# cbm_usb_v1_0a.net
KiCad netlist of a schematic drawn in EAGLE
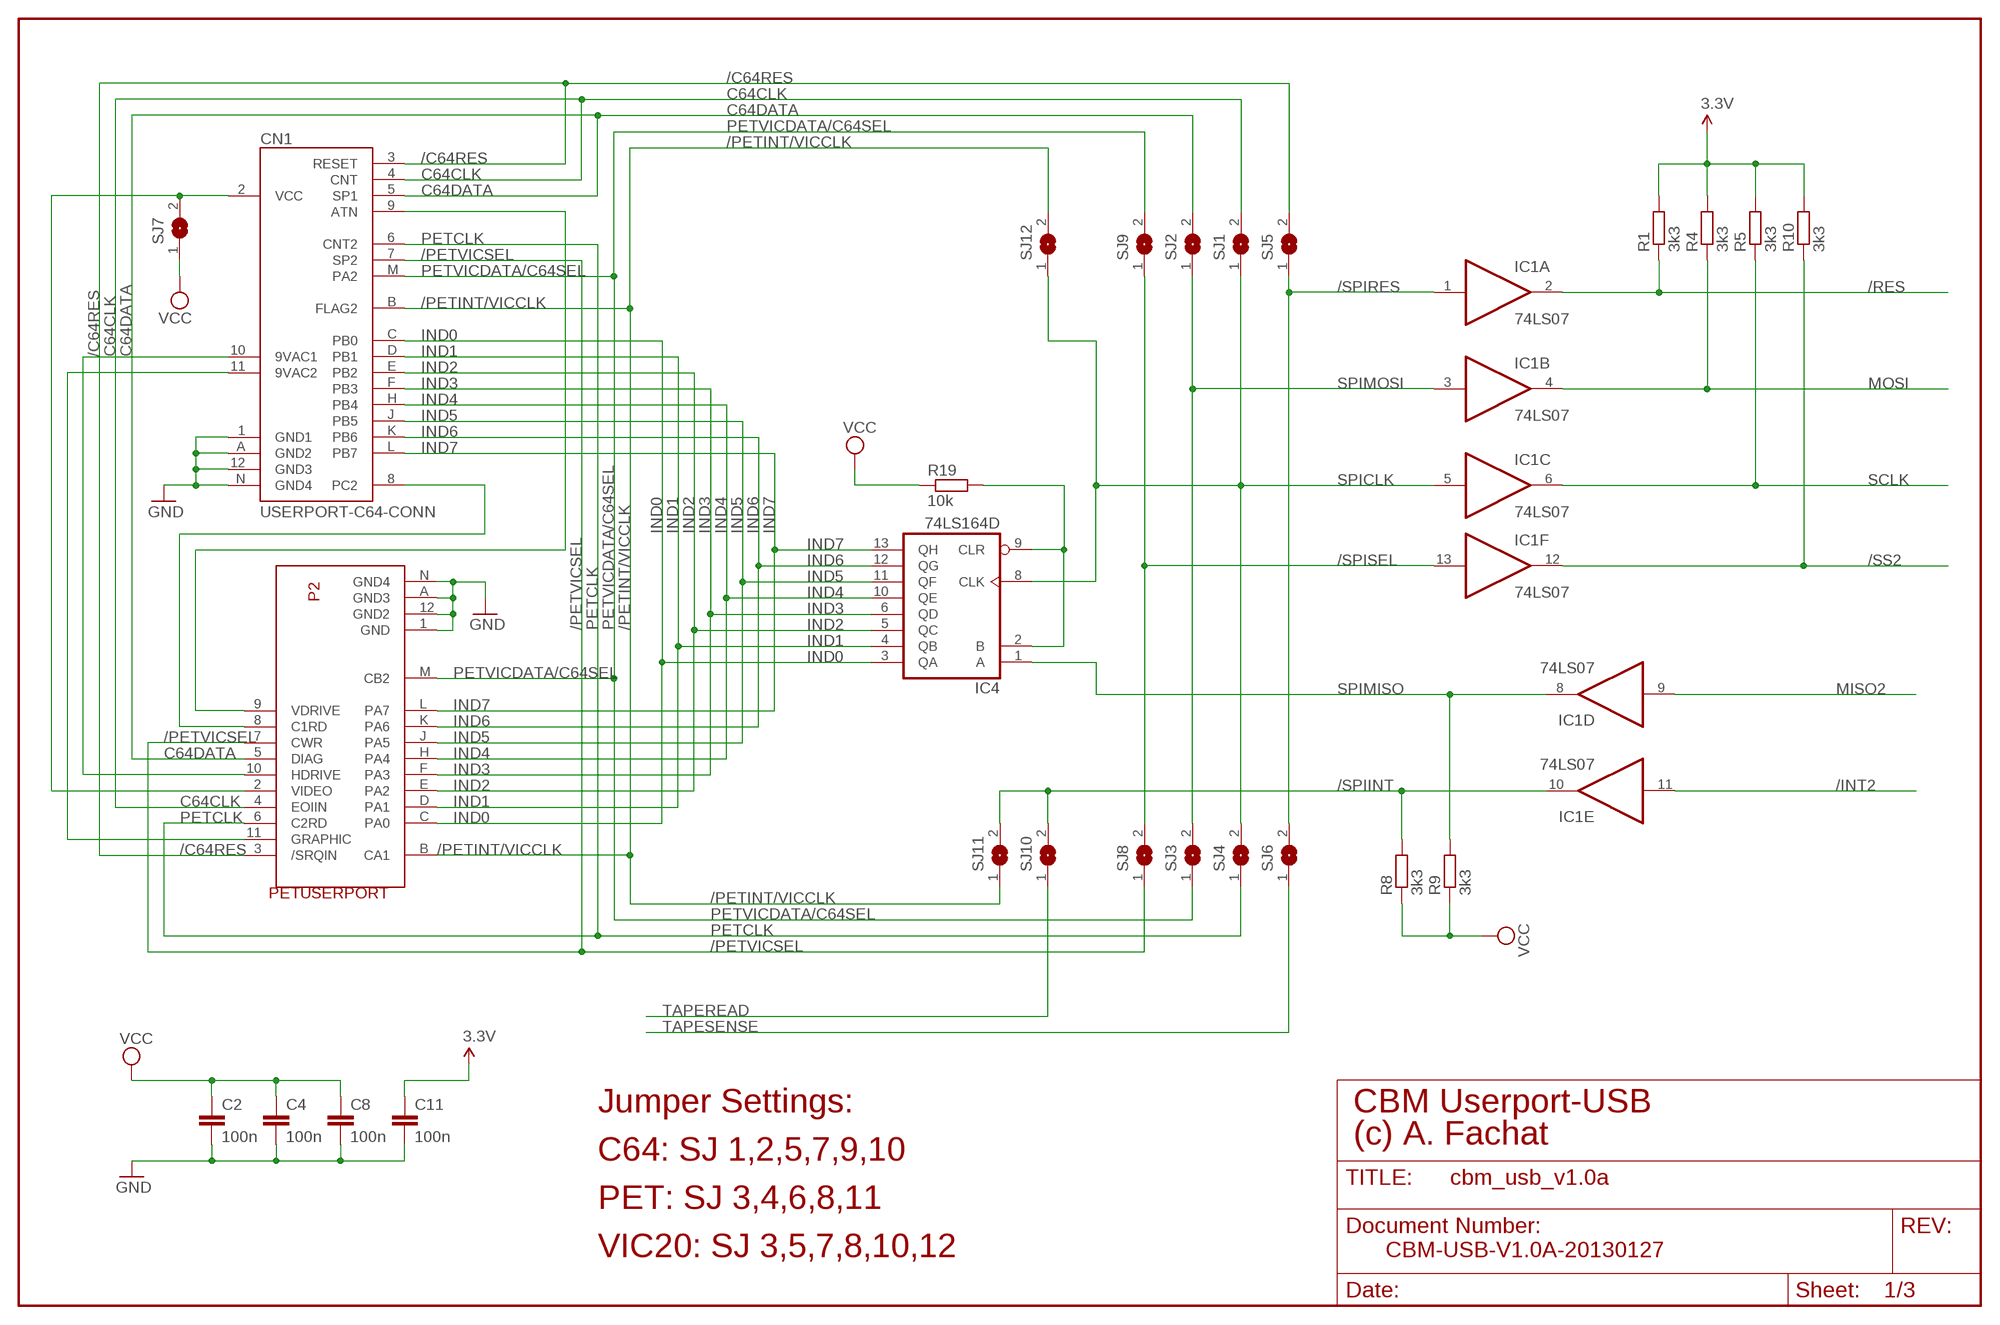
[diagram p0: schematic, sheet 1]
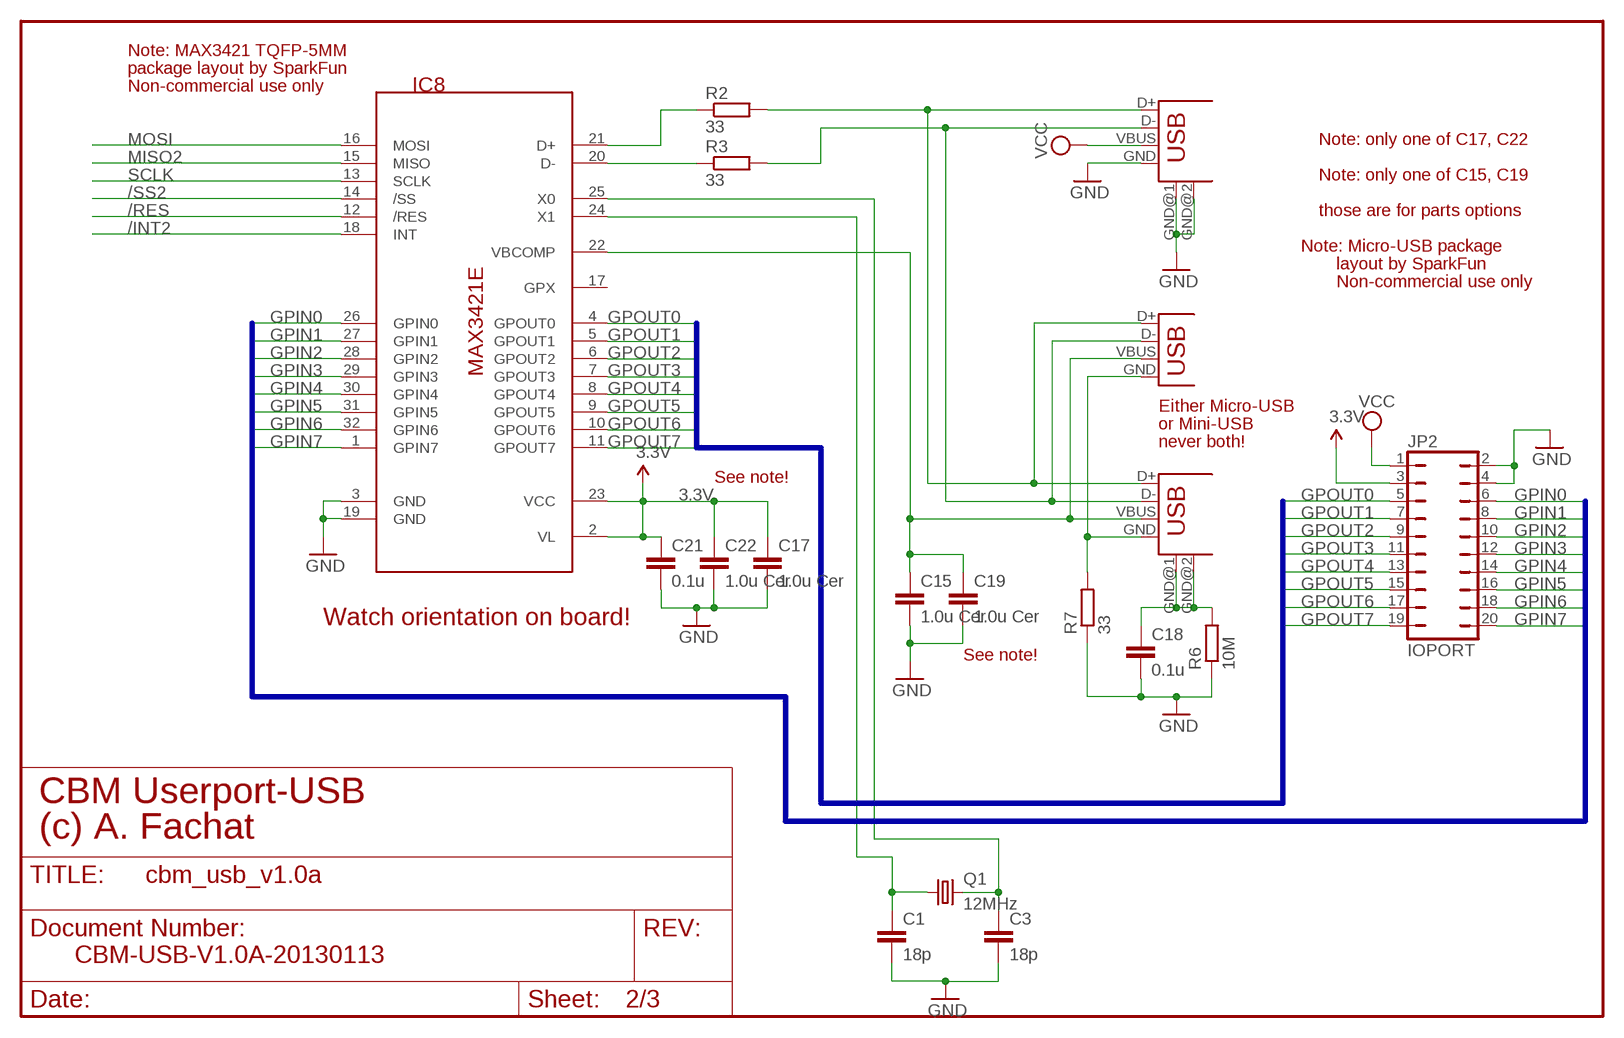
[diagram p1: schematic, sheet 2]
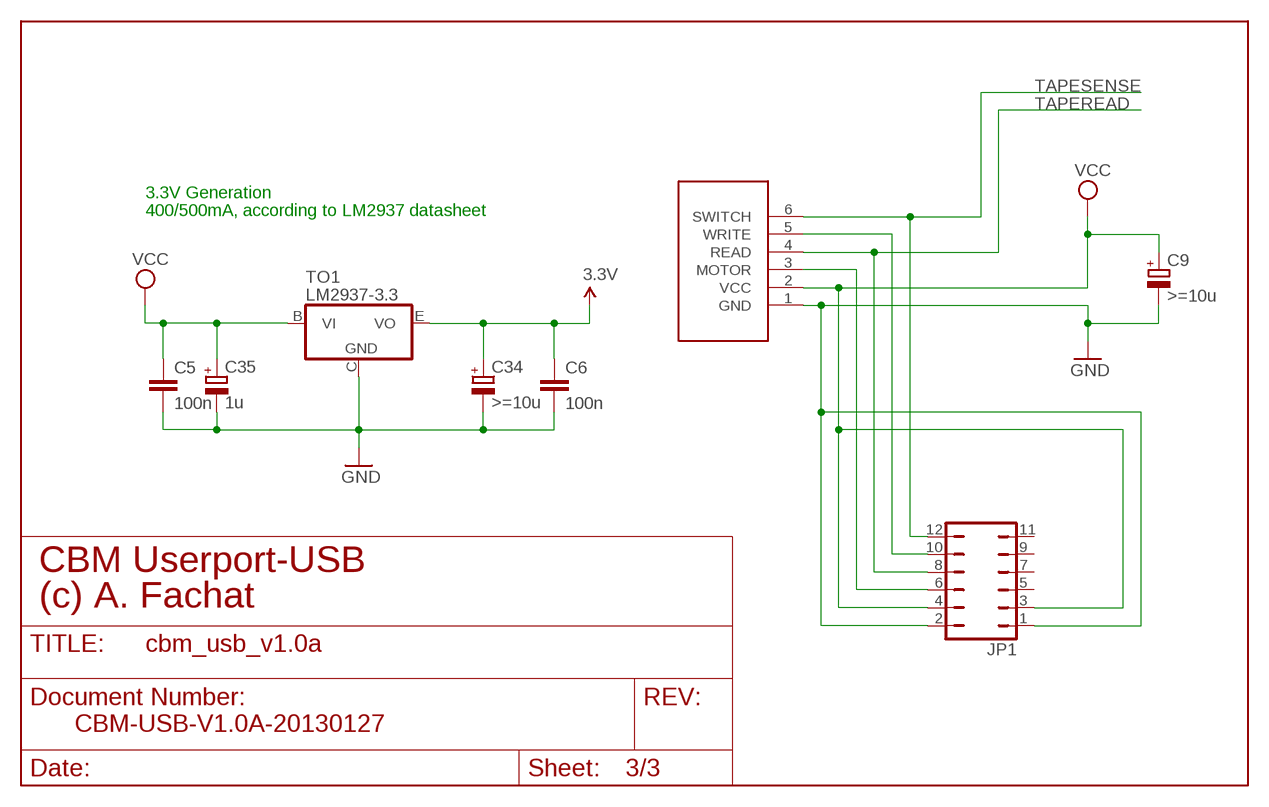
[diagram p2: schematic, sheet 3]

(export (version "E")
  (design (tool "Eeschema 10.0.6"))
  (components
    (comp (ref "C5")
      (value "100n")
      (footprint "eagle-import:C050-025X075")
      (libsource (lib "eagle-import") (part "C-EU050-025X075"))
    )
    (comp (ref "C6")
      (value "100n")
      (footprint "eagle-import:C050-025X075")
      (libsource (lib "eagle-import") (part "C-EU050-025X075"))
    )
    (comp (ref "C9")
      (value ">=10u")
      (footprint "eagle-import:E5-10,5")
      (libsource (lib "eagle-import") (part "CPOL-EUE5-10.5"))
    )
    (comp (ref "C34")
      (value ">=10u")
      (footprint "eagle-import:E5-8,5")
      (libsource (lib "eagle-import") (part "CPOL-EUE5-8.5"))
    )
    (comp (ref "C35")
      (value "1u")
      (footprint "eagle-import:E5-8,5")
      (libsource (lib "eagle-import") (part "CPOL-EUE5-8.5"))
    )
    (comp (ref "JP1")
      (value "JP6Q")
      (footprint "eagle-import:JP6Q")
      (libsource (lib "eagle-import") (part "JP6Q"))
    )
    (comp (ref "P3")
      (value "CBMTAPE")
      (footprint "eagle-import:JP6")
      (libsource (lib "eagle-import") (part "CBMTAPE"))
    )
    (comp (ref "TO1")
      (value "LM2937-3.3")
      (footprint "eagle-import:TO220H")
      (libsource (lib "eagle-import") (part "LM2937"))
    )
    (comp (ref "C2")
      (value "100n")
      (footprint "eagle-import:C050-025X075")
      (libsource (lib "eagle-import") (part "C-EU050-025X075"))
    )
    (comp (ref "C4")
      (value "100n")
      (footprint "eagle-import:C050-025X075")
      (libsource (lib "eagle-import") (part "C-EU050-025X075"))
    )
    (comp (ref "C8")
      (value "100n")
      (footprint "eagle-import:C050-025X075")
      (libsource (lib "eagle-import") (part "C-EU050-025X075"))
    )
    (comp (ref "C11")
      (value "100n")
      (footprint "eagle-import:C050-025X075")
      (libsource (lib "eagle-import") (part "C-EU050-025X075"))
    )
    (comp (ref "CN1")
      (value "USERPORT-C64-CONN")
      (footprint "eagle-import:UPS24CONN")
      (libsource (lib "eagle-import") (part "USERPORT-C64-CONN"))
    )
    (comp (ref "IC1")
      (value "74LS07")
      (footprint "eagle-import:SO14")
      (libsource (lib "eagle-import") (part "7407DLS"))
    )
    (comp (ref "IC4")
      (value "74LS164D")
      (footprint "eagle-import:SO14")
      (libsource (lib "eagle-import") (part "74164DLS"))
    )
    (comp (ref "P2")
      (value "PETUSERPORT")
      (footprint "eagle-import:FLAT24")
      (libsource (lib "eagle-import") (part "PETUSERPORT"))
    )
    (comp (ref "R1")
      (value "3k3")
      (footprint "eagle-import:0204_7")
      (libsource (lib "eagle-import") (part "R-EU_0204/7"))
    )
    (comp (ref "R4")
      (value "3k3")
      (footprint "eagle-import:0204_7")
      (libsource (lib "eagle-import") (part "R-EU_0204/7"))
    )
    (comp (ref "R5")
      (value "3k3")
      (footprint "eagle-import:0204_7")
      (libsource (lib "eagle-import") (part "R-EU_0204/7"))
    )
    (comp (ref "R8")
      (value "3k3")
      (footprint "eagle-import:0204_7")
      (libsource (lib "eagle-import") (part "R-EU_0204/7"))
    )
    (comp (ref "R9")
      (value "3k3")
      (footprint "eagle-import:0204_7")
      (libsource (lib "eagle-import") (part "R-EU_0204/7"))
    )
    (comp (ref "R10")
      (value "3k3")
      (footprint "eagle-import:0204_7")
      (libsource (lib "eagle-import") (part "R-EU_0204/7"))
    )
    (comp (ref "R19")
      (value "10k")
      (footprint "eagle-import:0204_7")
      (libsource (lib "eagle-import") (part "R-EU_0204/7"))
    )
    (comp (ref "SJ1")
      (value "SJW")
      (footprint "eagle-import:SJW")
      (libsource (lib "eagle-import") (part "SJW"))
    )
    (comp (ref "SJ2")
      (value "SJW")
      (footprint "eagle-import:SJW")
      (libsource (lib "eagle-import") (part "SJW"))
    )
    (comp (ref "SJ3")
      (value "SJW")
      (footprint "eagle-import:SJW")
      (libsource (lib "eagle-import") (part "SJW"))
    )
    (comp (ref "SJ4")
      (value "SJW")
      (footprint "eagle-import:SJW")
      (libsource (lib "eagle-import") (part "SJW"))
    )
    (comp (ref "SJ5")
      (value "SJW")
      (footprint "eagle-import:SJW")
      (libsource (lib "eagle-import") (part "SJW"))
    )
    (comp (ref "SJ6")
      (value "SJW")
      (footprint "eagle-import:SJW")
      (libsource (lib "eagle-import") (part "SJW"))
    )
    (comp (ref "SJ7")
      (value "SJW")
      (footprint "eagle-import:SJW")
      (libsource (lib "eagle-import") (part "SJW"))
    )
    (comp (ref "SJ8")
      (value "SJW")
      (footprint "eagle-import:SJW")
      (libsource (lib "eagle-import") (part "SJW"))
    )
    (comp (ref "SJ9")
      (value "SJW")
      (footprint "eagle-import:SJW")
      (libsource (lib "eagle-import") (part "SJW"))
    )
    (comp (ref "SJ10")
      (value "SJW")
      (footprint "eagle-import:SJW")
      (libsource (lib "eagle-import") (part "SJW"))
    )
    (comp (ref "SJ11")
      (value "SJW")
      (footprint "eagle-import:SJW")
      (libsource (lib "eagle-import") (part "SJW"))
    )
    (comp (ref "SJ12")
      (value "SJW")
      (footprint "eagle-import:SJW")
      (libsource (lib "eagle-import") (part "SJW"))
    )
    (comp (ref "C1")
      (value "18p")
      (footprint "eagle-import:C050-025X075")
      (libsource (lib "eagle-import") (part "C-EU050-025X075"))
    )
    (comp (ref "C3")
      (value "18p")
      (footprint "eagle-import:C050-025X075")
      (libsource (lib "eagle-import") (part "C-EU050-025X075"))
    )
    (comp (ref "C15")
      (value "1.0u Cer")
      (footprint "eagle-import:C0603")
      (libsource (lib "eagle-import") (part "C-EUC0603"))
    )
    (comp (ref "C17")
      (value "1.0u Cer")
      (footprint "eagle-import:C050-024X044")
      (libsource (lib "eagle-import") (part "C-EU050-024X044"))
    )
    (comp (ref "C18")
      (value "0.1u")
      (footprint "eagle-import:C050-025X075")
      (libsource (lib "eagle-import") (part "C-EU050-025X075"))
    )
    (comp (ref "C19")
      (value "1.0u Cer")
      (footprint "eagle-import:C050-024X044")
      (libsource (lib "eagle-import") (part "C-EU050-024X044"))
    )
    (comp (ref "C21")
      (value "0.1u")
      (footprint "eagle-import:C050-025X075")
      (libsource (lib "eagle-import") (part "C-EU050-025X075"))
    )
    (comp (ref "C22")
      (value "1.0u Cer")
      (footprint "eagle-import:C0603")
      (libsource (lib "eagle-import") (part "C-EUC0603"))
    )
    (comp (ref "IC8")
      (value "MAX3421E")
      (footprint "eagle-import:TQFP32-5MM")
      (libsource (lib "eagle-import") (part "MAX3421E"))
    )
    (comp (ref "JP2")
      (value "IOPORT")
      (footprint "eagle-import:JP10Q")
      (libsource (lib "eagle-import") (part "JP10Q"))
    )
    (comp (ref "Q1")
      (value "12MHz")
      (footprint "eagle-import:HC49U70")
      (libsource (lib "eagle-import") (part "CRYSTALHC49U70"))
    )
    (comp (ref "R2")
      (value "33")
      (footprint "eagle-import:0204_7")
      (libsource (lib "eagle-import") (part "R-EU_0204/7"))
    )
    (comp (ref "R3")
      (value "33")
      (footprint "eagle-import:0204_7")
      (libsource (lib "eagle-import") (part "R-EU_0204/7"))
    )
    (comp (ref "R6")
      (value "10M")
      (footprint "eagle-import:0204_7")
      (libsource (lib "eagle-import") (part "R-EU_0204/7"))
    )
    (comp (ref "R7")
      (value "33")
      (footprint "eagle-import:0204_7")
      (libsource (lib "eagle-import") (part "R-EU_0204/7"))
    )
    (comp (ref "USB1")
      (value "USB-A-H")
      (footprint "eagle-import:USB-A-H")
      (libsource (lib "eagle-import") (part "con-usb-2_USB-A-H"))
    )
    (comp (ref "USB2")
      (value "USB-MB-H")
      (footprint "eagle-import:USB-MB-H")
      (libsource (lib "eagle-import") (part "con-usb-2_USB-MB-H"))
    )
    (comp (ref "X1")
      (value "USB-MICROB")
      (footprint "eagle-import:USB-MICROB")
      (libsource (lib "eagle-import") (part "USB-MICROB"))
    )
  )
  (nets
    (net (code "1") (name "3.3V") (class "Default")
      (node (ref "C11") (pin "1") (pinfunction "1_1") (pintype "passive"))
      (node (ref "C17") (pin "1") (pinfunction "1_1") (pintype "passive"))
      (node (ref "C21") (pin "1") (pinfunction "1_1") (pintype "passive"))
      (node (ref "C22") (pin "1") (pinfunction "1_1") (pintype "passive"))
      (node (ref "C34") (pin "+") (pinfunction "+_+") (pintype "passive"))
      (node (ref "C6") (pin "1") (pinfunction "1_1") (pintype "passive"))
      (node (ref "IC8") (pin "2") (pinfunction "VL_2") (pintype "power_in"))
      (node (ref "IC8") (pin "23") (pinfunction "VCC_23") (pintype "power_in"))
      (node (ref "JP2") (pin "3") (pinfunction "3_3") (pintype "passive"))
      (node (ref "R1") (pin "2") (pinfunction "2_2") (pintype "passive"))
      (node (ref "R10") (pin "2") (pinfunction "2_2") (pintype "passive"))
      (node (ref "R4") (pin "2") (pinfunction "2_2") (pintype "passive"))
      (node (ref "R5") (pin "2") (pinfunction "2_2") (pintype "passive"))
      (node (ref "TO1") (pin "E") (pinfunction "VO_E") (pintype "passive"))
    )
    (net (code "2") (name "C64CLK") (class "Default")
      (node (ref "CN1") (pin "4") (pinfunction "CNT_4") (pintype "bidirectional"))
      (node (ref "P2") (pin "4") (pinfunction "EOIIN_4") (pintype "bidirectional"))
      (node (ref "SJ1") (pin "2") (pinfunction "2_2") (pintype "passive"))
    )
    (net (code "3") (name "C64DATA") (class "Default")
      (node (ref "CN1") (pin "5") (pinfunction "SP1_5") (pintype "bidirectional"))
      (node (ref "P2") (pin "5") (pinfunction "DIAG_5") (pintype "bidirectional"))
      (node (ref "SJ2") (pin "2") (pinfunction "2_2") (pintype "passive"))
    )
    (net (code "4") (name "GND") (class "Default")
      (node (ref "C1") (pin "2") (pinfunction "2_2") (pintype "passive"))
      (node (ref "C11") (pin "2") (pinfunction "2_2") (pintype "passive"))
      (node (ref "C15") (pin "2") (pinfunction "2_2") (pintype "passive"))
      (node (ref "C17") (pin "2") (pinfunction "2_2") (pintype "passive"))
      (node (ref "C18") (pin "2") (pinfunction "2_2") (pintype "passive"))
      (node (ref "C19") (pin "2") (pinfunction "2_2") (pintype "passive"))
      (node (ref "C2") (pin "2") (pinfunction "2_2") (pintype "passive"))
      (node (ref "C21") (pin "2") (pinfunction "2_2") (pintype "passive"))
      (node (ref "C22") (pin "2") (pinfunction "2_2") (pintype "passive"))
      (node (ref "C3") (pin "2") (pinfunction "2_2") (pintype "passive"))
      (node (ref "C34") (pin "-") (pinfunction "-_-") (pintype "passive"))
      (node (ref "C35") (pin "-") (pinfunction "-_-") (pintype "passive"))
      (node (ref "C4") (pin "2") (pinfunction "2_2") (pintype "passive"))
      (node (ref "C5") (pin "2") (pinfunction "2_2") (pintype "passive"))
      (node (ref "C6") (pin "2") (pinfunction "2_2") (pintype "passive"))
      (node (ref "C8") (pin "2") (pinfunction "2_2") (pintype "passive"))
      (node (ref "C9") (pin "-") (pinfunction "-_-") (pintype "passive"))
      (node (ref "CN1") (pin "1") (pinfunction "GND1_1") (pintype "passive"))
      (node (ref "CN1") (pin "12") (pinfunction "GND3_12") (pintype "passive"))
      (node (ref "CN1") (pin "A") (pinfunction "GND2_A") (pintype "passive"))
      (node (ref "CN1") (pin "N") (pinfunction "GND4_N") (pintype "passive"))
      (node (ref "IC8") (pin "19") (pinfunction "GND_19") (pintype "power_in"))
      (node (ref "IC8") (pin "3") (pinfunction "GND_3") (pintype "power_in"))
      (node (ref "JP1") (pin "1") (pinfunction "1_1") (pintype "passive"))
      (node (ref "JP1") (pin "2") (pinfunction "2_2") (pintype "passive"))
      (node (ref "JP2") (pin "2") (pinfunction "2_2") (pintype "passive"))
      (node (ref "JP2") (pin "4") (pinfunction "4_4") (pintype "passive"))
      (node (ref "P2") (pin "1") (pinfunction "GND_1") (pintype "bidirectional"))
      (node (ref "P2") (pin "12") (pinfunction "GND2_12") (pintype "bidirectional"))
      (node (ref "P2") (pin "A") (pinfunction "GND3_A") (pintype "bidirectional"))
      (node (ref "P2") (pin "N") (pinfunction "GND4_N") (pintype "bidirectional"))
      (node (ref "P3") (pin "1") (pinfunction "GND_1") (pintype "bidirectional"))
      (node (ref "R6") (pin "1") (pinfunction "1_1") (pintype "passive"))
      (node (ref "R7") (pin "1") (pinfunction "1_1") (pintype "passive"))
      (node (ref "TO1") (pin "C") (pinfunction "GND_C") (pintype "passive"))
      (node (ref "USB1") (pin "GND") (pinfunction "GND_GND") (pintype "bidirectional"))
      (node (ref "USB1") (pin "GND@1") (pinfunction "GND_GND@1") (pintype "bidirectional"))
      (node (ref "USB1") (pin "GND@2") (pinfunction "GND_GND@2") (pintype "bidirectional"))
    )
    (net (code "5") (name "GPIN0") (class "Default")
      (node (ref "IC8") (pin "26") (pinfunction "GPIN0_26") (pintype "input"))
      (node (ref "JP2") (pin "6") (pinfunction "6_6") (pintype "passive"))
    )
    (net (code "6") (name "GPIN1") (class "Default")
      (node (ref "IC8") (pin "27") (pinfunction "GPIN1_27") (pintype "input"))
      (node (ref "JP2") (pin "8") (pinfunction "8_8") (pintype "passive"))
    )
    (net (code "7") (name "GPIN2") (class "Default")
      (node (ref "IC8") (pin "28") (pinfunction "GPIN2_28") (pintype "input"))
      (node (ref "JP2") (pin "10") (pinfunction "10_10") (pintype "passive"))
    )
    (net (code "8") (name "GPIN3") (class "Default")
      (node (ref "IC8") (pin "29") (pinfunction "GPIN3_29") (pintype "input"))
      (node (ref "JP2") (pin "12") (pinfunction "12_12") (pintype "passive"))
    )
    (net (code "9") (name "GPIN4") (class "Default")
      (node (ref "IC8") (pin "30") (pinfunction "GPIN4_30") (pintype "input"))
      (node (ref "JP2") (pin "14") (pinfunction "14_14") (pintype "passive"))
    )
    (net (code "10") (name "GPIN5") (class "Default")
      (node (ref "IC8") (pin "31") (pinfunction "GPIN5_31") (pintype "input"))
      (node (ref "JP2") (pin "16") (pinfunction "16_16") (pintype "passive"))
    )
    (net (code "11") (name "GPIN6") (class "Default")
      (node (ref "IC8") (pin "32") (pinfunction "GPIN6_32") (pintype "input"))
      (node (ref "JP2") (pin "18") (pinfunction "18_18") (pintype "passive"))
    )
    (net (code "12") (name "GPIN7") (class "Default")
      (node (ref "IC8") (pin "1") (pinfunction "GPIN7_1") (pintype "input"))
      (node (ref "JP2") (pin "20") (pinfunction "20_20") (pintype "passive"))
    )
    (net (code "13") (name "GPOUT0") (class "Default")
      (node (ref "IC8") (pin "4") (pinfunction "GPOUT0_4") (pintype "output"))
      (node (ref "JP2") (pin "5") (pinfunction "5_5") (pintype "passive"))
    )
    (net (code "14") (name "GPOUT1") (class "Default")
      (node (ref "IC8") (pin "5") (pinfunction "GPOUT1_5") (pintype "output"))
      (node (ref "JP2") (pin "7") (pinfunction "7_7") (pintype "passive"))
    )
    (net (code "15") (name "GPOUT2") (class "Default")
      (node (ref "IC8") (pin "6") (pinfunction "GPOUT2_6") (pintype "output"))
      (node (ref "JP2") (pin "9") (pinfunction "9_9") (pintype "passive"))
    )
    (net (code "16") (name "GPOUT3") (class "Default")
      (node (ref "IC8") (pin "7") (pinfunction "GPOUT3_7") (pintype "output"))
      (node (ref "JP2") (pin "11") (pinfunction "11_11") (pintype "passive"))
    )
    (net (code "17") (name "GPOUT4") (class "Default")
      (node (ref "IC8") (pin "8") (pinfunction "GPOUT4_8") (pintype "output"))
      (node (ref "JP2") (pin "13") (pinfunction "13_13") (pintype "passive"))
    )
    (net (code "18") (name "GPOUT5") (class "Default")
      (node (ref "IC8") (pin "9") (pinfunction "GPOUT5_9") (pintype "output"))
      (node (ref "JP2") (pin "15") (pinfunction "15_15") (pintype "passive"))
    )
    (net (code "19") (name "GPOUT6") (class "Default")
      (node (ref "IC8") (pin "10") (pinfunction "GPOUT6_10") (pintype "output"))
      (node (ref "JP2") (pin "17") (pinfunction "17_17") (pintype "passive"))
    )
    (net (code "20") (name "GPOUT7") (class "Default")
      (node (ref "IC8") (pin "11") (pinfunction "GPOUT7_11") (pintype "output"))
      (node (ref "JP2") (pin "19") (pinfunction "19_19") (pintype "passive"))
    )
    (net (code "21") (name "IND0") (class "Default")
      (node (ref "CN1") (pin "C") (pinfunction "PB0_C") (pintype "bidirectional"))
      (node (ref "IC4") (pin "3") (pinfunction "QA_3") (pintype "output"))
      (node (ref "P2") (pin "C") (pinfunction "PA0_C") (pintype "bidirectional"))
    )
    (net (code "22") (name "IND1") (class "Default")
      (node (ref "CN1") (pin "D") (pinfunction "PB1_D") (pintype "bidirectional"))
      (node (ref "IC4") (pin "4") (pinfunction "QB_4") (pintype "output"))
      (node (ref "P2") (pin "D") (pinfunction "PA1_D") (pintype "bidirectional"))
    )
    (net (code "23") (name "IND2") (class "Default")
      (node (ref "CN1") (pin "E") (pinfunction "PB2_E") (pintype "bidirectional"))
      (node (ref "IC4") (pin "5") (pinfunction "QC_5") (pintype "output"))
      (node (ref "P2") (pin "E") (pinfunction "PA2_E") (pintype "bidirectional"))
    )
    (net (code "24") (name "IND3") (class "Default")
      (node (ref "CN1") (pin "F") (pinfunction "PB3_F") (pintype "bidirectional"))
      (node (ref "IC4") (pin "6") (pinfunction "QD_6") (pintype "output"))
      (node (ref "P2") (pin "F") (pinfunction "PA3_F") (pintype "bidirectional"))
    )
    (net (code "25") (name "IND4") (class "Default")
      (node (ref "CN1") (pin "H") (pinfunction "PB4_H") (pintype "bidirectional"))
      (node (ref "IC4") (pin "10") (pinfunction "QE_10") (pintype "output"))
      (node (ref "P2") (pin "H") (pinfunction "PA4_H") (pintype "bidirectional"))
    )
    (net (code "26") (name "IND5") (class "Default")
      (node (ref "CN1") (pin "J") (pinfunction "PB5_J") (pintype "bidirectional"))
      (node (ref "IC4") (pin "11") (pinfunction "QF_11") (pintype "output"))
      (node (ref "P2") (pin "J") (pinfunction "PA5_J") (pintype "bidirectional"))
    )
    (net (code "27") (name "IND6") (class "Default")
      (node (ref "CN1") (pin "K") (pinfunction "PB6_K") (pintype "bidirectional"))
      (node (ref "IC4") (pin "12") (pinfunction "QG_12") (pintype "output"))
      (node (ref "P2") (pin "K") (pinfunction "PA6_K") (pintype "bidirectional"))
    )
    (net (code "28") (name "IND7") (class "Default")
      (node (ref "CN1") (pin "L") (pinfunction "PB7_L") (pintype "bidirectional"))
      (node (ref "IC4") (pin "13") (pinfunction "QH_13") (pintype "output"))
      (node (ref "P2") (pin "L") (pinfunction "PA7_L") (pintype "bidirectional"))
    )
    (net (code "29") (name "MISO2") (class "Default")
      (node (ref "IC1") (pin "9") (pinfunction "I_9") (pintype "input"))
      (node (ref "IC8") (pin "15") (pinfunction "MISO_15") (pintype "output"))
    )
    (net (code "30") (name "MOSI") (class "Default")
      (node (ref "IC1") (pin "4") (pinfunction "O_4") (pintype "open_collector"))
      (node (ref "IC8") (pin "16") (pinfunction "MOSI_16") (pintype "input"))
      (node (ref "R4") (pin "1") (pinfunction "1_1") (pintype "passive"))
    )
    (net (code "31") (name "Net-(C18-Pad1)") (class "Default")
      (node (ref "C18") (pin "1") (pinfunction "1_1") (pintype "passive"))
      (node (ref "R6") (pin "2") (pinfunction "2_2") (pintype "passive"))
      (node (ref "USB2") (pin "GND@1") (pinfunction "GND_GND@1") (pintype "bidirectional"))
      (node (ref "USB2") (pin "GND@2") (pinfunction "GND_GND@2") (pintype "bidirectional"))
    )
    (net (code "32") (name "Net-(CN1-9VAC1)") (class "Default")
      (node (ref "CN1") (pin "10") (pinfunction "9VAC1_10") (pintype "output"))
      (node (ref "P2") (pin "10") (pinfunction "HDRIVE_10") (pintype "bidirectional"))
    )
    (net (code "33") (name "Net-(CN1-9VAC2)") (class "Default")
      (node (ref "CN1") (pin "11") (pinfunction "9VAC2_11") (pintype "output"))
      (node (ref "P2") (pin "11") (pinfunction "GRAPHIC_11") (pintype "bidirectional"))
    )
    (net (code "34") (name "Net-(CN1-ATN)") (class "Default")
      (node (ref "CN1") (pin "9") (pinfunction "ATN_9") (pintype "bidirectional"))
      (node (ref "P2") (pin "9") (pinfunction "VDRIVE_9") (pintype "bidirectional"))
    )
    (net (code "35") (name "Net-(CN1-PC2)") (class "Default")
      (node (ref "CN1") (pin "8") (pinfunction "PC2_8") (pintype "bidirectional"))
      (node (ref "P2") (pin "8") (pinfunction "C1RD_8") (pintype "bidirectional"))
    )
    (net (code "36") (name "Net-(CN1-VCC)") (class "Default")
      (node (ref "CN1") (pin "2") (pinfunction "VCC_2") (pintype "passive"))
      (node (ref "P2") (pin "2") (pinfunction "VIDEO_2") (pintype "bidirectional"))
      (node (ref "SJ7") (pin "2") (pinfunction "2_2") (pintype "passive"))
    )
    (net (code "37") (name "Net-(IC4A-B)") (class "Default")
      (node (ref "IC4") (pin "2") (pinfunction "B_2") (pintype "input"))
      (node (ref "IC4") (pin "9") (pinfunction "CLR_9") (pintype "input"))
      (node (ref "R19") (pin "2") (pinfunction "2_2") (pintype "passive"))
    )
    (net (code "38") (name "Net-(IC8-D+)") (class "Default")
      (node (ref "IC8") (pin "21") (pinfunction "D+_21") (pintype "bidirectional"))
      (node (ref "R2") (pin "1") (pinfunction "1_1") (pintype "passive"))
    )
    (net (code "39") (name "Net-(IC8-D-)") (class "Default")
      (node (ref "IC8") (pin "20") (pinfunction "D-_20") (pintype "bidirectional"))
      (node (ref "R3") (pin "1") (pinfunction "1_1") (pintype "passive"))
    )
    (net (code "40") (name "Net-(IC8-VBCOMP)") (class "Default")
      (node (ref "C15") (pin "1") (pinfunction "1_1") (pintype "passive"))
      (node (ref "C19") (pin "1") (pinfunction "1_1") (pintype "passive"))
      (node (ref "IC8") (pin "22") (pinfunction "VBCOMP_22") (pintype "bidirectional"))
      (node (ref "USB2") (pin "VBUS") (pinfunction "VBUS_VBUS") (pintype "bidirectional"))
      (node (ref "X1") (pin "VBUS") (pinfunction "VBUS_VBUS") (pintype "bidirectional"))
    )
    (net (code "41") (name "Net-(IC8-X0)") (class "Default")
      (node (ref "C3") (pin "1") (pinfunction "1_1") (pintype "passive"))
      (node (ref "IC8") (pin "25") (pinfunction "X0_25") (pintype "bidirectional"))
      (node (ref "Q1") (pin "2") (pinfunction "2_2") (pintype "passive"))
    )
    (net (code "42") (name "Net-(IC8-X1)") (class "Default")
      (node (ref "C1") (pin "1") (pinfunction "1_1") (pintype "passive"))
      (node (ref "IC8") (pin "24") (pinfunction "X1_24") (pintype "bidirectional"))
      (node (ref "Q1") (pin "1") (pinfunction "1_1") (pintype "passive"))
    )
    (net (code "43") (name "Net-(P3-MOTOR)") (class "Default")
      (node (ref "JP1") (pin "6") (pinfunction "6_6") (pintype "passive"))
      (node (ref "P3") (pin "3") (pinfunction "MOTOR_3") (pintype "bidirectional"))
    )
    (net (code "44") (name "Net-(P3-WRITE)") (class "Default")
      (node (ref "JP1") (pin "10") (pinfunction "10_10") (pintype "passive"))
      (node (ref "P3") (pin "5") (pinfunction "WRITE_5") (pintype "bidirectional"))
    )
    (net (code "45") (name "Net-(R2-Pad2)") (class "Default")
      (node (ref "R2") (pin "2") (pinfunction "2_2") (pintype "passive"))
      (node (ref "USB1") (pin "D+") (pinfunction "D+_D+") (pintype "bidirectional"))
      (node (ref "USB2") (pin "D+") (pinfunction "D+_D+") (pintype "bidirectional"))
      (node (ref "X1") (pin "D+") (pinfunction "D+_D+") (pintype "bidirectional"))
    )
    (net (code "46") (name "Net-(R3-Pad2)") (class "Default")
      (node (ref "R3") (pin "2") (pinfunction "2_2") (pintype "passive"))
      (node (ref "USB1") (pin "D-") (pinfunction "D-_D-") (pintype "bidirectional"))
      (node (ref "USB2") (pin "D-") (pinfunction "D-_D-") (pintype "bidirectional"))
      (node (ref "X1") (pin "D-") (pinfunction "D-_D-") (pintype "bidirectional"))
    )
    (net (code "47") (name "Net-(R7-Pad2)") (class "Default")
      (node (ref "R7") (pin "2") (pinfunction "2_2") (pintype "passive"))
      (node (ref "USB2") (pin "GND") (pinfunction "GND_GND") (pintype "bidirectional"))
      (node (ref "X1") (pin "GND") (pinfunction "GND_GND") (pintype "bidirectional"))
    )
    (net (code "48") (name "PETCLK") (class "Default")
      (node (ref "CN1") (pin "6") (pinfunction "CNT2_6") (pintype "bidirectional"))
      (node (ref "P2") (pin "6") (pinfunction "C2RD_6") (pintype "bidirectional"))
      (node (ref "SJ4") (pin "1") (pinfunction "1_1") (pintype "passive"))
    )
    (net (code "49") (name "PETVICDATA{slash}C64SEL") (class "Default")
      (node (ref "CN1") (pin "M") (pinfunction "PA2_M") (pintype "bidirectional"))
      (node (ref "P2") (pin "M") (pinfunction "CB2_M") (pintype "bidirectional"))
      (node (ref "SJ3") (pin "1") (pinfunction "1_1") (pintype "passive"))
      (node (ref "SJ9") (pin "2") (pinfunction "2_2") (pintype "passive"))
    )
    (net (code "50") (name "SCLK") (class "Default")
      (node (ref "IC1") (pin "6") (pinfunction "O_6") (pintype "open_collector"))
      (node (ref "IC8") (pin "13") (pinfunction "SCLK_13") (pintype "input"))
      (node (ref "R5") (pin "1") (pinfunction "1_1") (pintype "passive"))
    )
    (net (code "51") (name "SPICLK") (class "Default")
      (node (ref "IC1") (pin "5") (pinfunction "I_5") (pintype "input"))
      (node (ref "IC4") (pin "8") (pinfunction "CLK_8") (pintype "input"))
      (node (ref "SJ1") (pin "1") (pinfunction "1_1") (pintype "passive"))
      (node (ref "SJ12") (pin "1") (pinfunction "1_1") (pintype "passive"))
      (node (ref "SJ4") (pin "2") (pinfunction "2_2") (pintype "passive"))
    )
    (net (code "52") (name "SPIMISO") (class "Default")
      (node (ref "IC1") (pin "8") (pinfunction "O_8") (pintype "open_collector"))
      (node (ref "IC4") (pin "1") (pinfunction "A_1") (pintype "input"))
      (node (ref "R9") (pin "2") (pinfunction "2_2") (pintype "passive"))
    )
    (net (code "53") (name "SPIMOSI") (class "Default")
      (node (ref "IC1") (pin "3") (pinfunction "I_3") (pintype "input"))
      (node (ref "SJ2") (pin "1") (pinfunction "1_1") (pintype "passive"))
      (node (ref "SJ3") (pin "2") (pinfunction "2_2") (pintype "passive"))
    )
    (net (code "54") (name "TAPEREAD") (class "Default")
      (node (ref "JP1") (pin "8") (pinfunction "8_8") (pintype "passive"))
      (node (ref "P3") (pin "4") (pinfunction "READ_4") (pintype "bidirectional"))
      (node (ref "SJ10") (pin "1") (pinfunction "1_1") (pintype "passive"))
    )
    (net (code "55") (name "TAPESENSE") (class "Default")
      (node (ref "JP1") (pin "12") (pinfunction "12_12") (pintype "passive"))
      (node (ref "P3") (pin "6") (pinfunction "SWITCH_6") (pintype "bidirectional"))
      (node (ref "SJ6") (pin "1") (pinfunction "1_1") (pintype "passive"))
    )
    (net (code "56") (name "VCC") (class "Default")
      (node (ref "C2") (pin "1") (pinfunction "1_1") (pintype "passive"))
      (node (ref "C35") (pin "+") (pinfunction "+_+") (pintype "passive"))
      (node (ref "C4") (pin "1") (pinfunction "1_1") (pintype "passive"))
      (node (ref "C5") (pin "1") (pinfunction "1_1") (pintype "passive"))
      (node (ref "C8") (pin "1") (pinfunction "1_1") (pintype "passive"))
      (node (ref "C9") (pin "+") (pinfunction "+_+") (pintype "passive"))
      (node (ref "JP1") (pin "3") (pinfunction "3_3") (pintype "passive"))
      (node (ref "JP1") (pin "4") (pinfunction "4_4") (pintype "passive"))
      (node (ref "JP2") (pin "1") (pinfunction "1_1") (pintype "passive"))
      (node (ref "P3") (pin "2") (pinfunction "VCC_2") (pintype "bidirectional"))
      (node (ref "R19") (pin "1") (pinfunction "1_1") (pintype "passive"))
      (node (ref "R8") (pin "1") (pinfunction "1_1") (pintype "passive"))
      (node (ref "R9") (pin "1") (pinfunction "1_1") (pintype "passive"))
      (node (ref "SJ7") (pin "1") (pinfunction "1_1") (pintype "passive"))
      (node (ref "TO1") (pin "B") (pinfunction "VI_B") (pintype "input"))
      (node (ref "USB1") (pin "VBUS") (pinfunction "VBUS_VBUS") (pintype "bidirectional"))
    )
    (net (code "57") (name "unconnected-(IC8-GPX-Pad17)") (class "Default")
      (node (ref "IC8") (pin "17") (pinfunction "GPX_17") (pintype "bidirectional"))
    )
    (net (code "58") (name "unconnected-(JP1-Pad5)") (class "Default")
      (node (ref "JP1") (pin "5") (pinfunction "5_5") (pintype "passive"))
    )
    (net (code "59") (name "unconnected-(JP1-Pad7)") (class "Default")
      (node (ref "JP1") (pin "7") (pinfunction "7_7") (pintype "passive"))
    )
    (net (code "60") (name "unconnected-(JP1-Pad9)") (class "Default")
      (node (ref "JP1") (pin "9") (pinfunction "9_9") (pintype "passive"))
    )
    (net (code "61") (name "unconnected-(JP1-Pad11)") (class "Default")
      (node (ref "JP1") (pin "11") (pinfunction "11_11") (pintype "passive"))
    )
    (net (code "62") (name "{slash}C64RES") (class "Default")
      (node (ref "CN1") (pin "3") (pinfunction "RESET_3") (pintype "bidirectional"))
      (node (ref "P2") (pin "3") (pinfunction "/SRQIN_3") (pintype "bidirectional"))
      (node (ref "SJ5") (pin "2") (pinfunction "2_2") (pintype "passive"))
    )
    (net (code "63") (name "{slash}INT2") (class "Default")
      (node (ref "IC1") (pin "11") (pinfunction "I_11") (pintype "input"))
      (node (ref "IC8") (pin "18") (pinfunction "INT_18") (pintype "output"))
    )
    (net (code "64") (name "{slash}PETINT{slash}VICCLK") (class "Default")
      (node (ref "CN1") (pin "B") (pinfunction "FLAG2_B") (pintype "input"))
      (node (ref "P2") (pin "B") (pinfunction "CA1_B") (pintype "bidirectional"))
      (node (ref "SJ11") (pin "1") (pinfunction "1_1") (pintype "passive"))
      (node (ref "SJ12") (pin "2") (pinfunction "2_2") (pintype "passive"))
    )
    (net (code "65") (name "{slash}PETVICSEL") (class "Default")
      (node (ref "CN1") (pin "7") (pinfunction "SP2_7") (pintype "bidirectional"))
      (node (ref "P2") (pin "7") (pinfunction "CWR_7") (pintype "bidirectional"))
      (node (ref "SJ8") (pin "1") (pinfunction "1_1") (pintype "passive"))
    )
    (net (code "66") (name "{slash}RES") (class "Default")
      (node (ref "IC1") (pin "2") (pinfunction "O_2") (pintype "open_collector"))
      (node (ref "IC8") (pin "12") (pinfunction "/RES_12") (pintype "input"))
      (node (ref "R1") (pin "1") (pinfunction "1_1") (pintype "passive"))
    )
    (net (code "67") (name "{slash}SPIINT") (class "Default")
      (node (ref "IC1") (pin "10") (pinfunction "O_10") (pintype "open_collector"))
      (node (ref "R8") (pin "2") (pinfunction "2_2") (pintype "passive"))
      (node (ref "SJ10") (pin "2") (pinfunction "2_2") (pintype "passive"))
      (node (ref "SJ11") (pin "2") (pinfunction "2_2") (pintype "passive"))
    )
    (net (code "68") (name "{slash}SPIRES") (class "Default")
      (node (ref "IC1") (pin "1") (pinfunction "I_1") (pintype "input"))
      (node (ref "SJ5") (pin "1") (pinfunction "1_1") (pintype "passive"))
      (node (ref "SJ6") (pin "2") (pinfunction "2_2") (pintype "passive"))
    )
    (net (code "69") (name "{slash}SPISEL") (class "Default")
      (node (ref "IC1") (pin "13") (pinfunction "I_13") (pintype "input"))
      (node (ref "SJ8") (pin "2") (pinfunction "2_2") (pintype "passive"))
      (node (ref "SJ9") (pin "1") (pinfunction "1_1") (pintype "passive"))
    )
    (net (code "70") (name "{slash}SS2") (class "Default")
      (node (ref "IC1") (pin "12") (pinfunction "O_12") (pintype "open_collector"))
      (node (ref "IC8") (pin "14") (pinfunction "/SS_14") (pintype "input"))
      (node (ref "R10") (pin "1") (pinfunction "1_1") (pintype "passive"))
    )
  )
)
